# CH340G_adapter.net
KiCad netlist of a schematic drawn in EAGLE
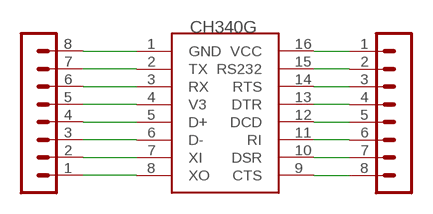
[diagram p0: schematic, sheet 1]

(export (version "E")
  (design (tool "Eeschema 10.0.6"))
  (components
    (comp (ref "SV1")
      (value "MA08-1")
      (footprint "eagle-import:MA08-1")
      (libsource (lib "eagle-import") (part "MA08-1"))
    )
    (comp (ref "SV2")
      (value "MA08-1")
      (footprint "eagle-import:MA08-1")
      (libsource (lib "eagle-import") (part "MA08-1"))
    )
    (comp (ref "U$1")
      (value "CH340G")
      (footprint "eagle-import:SOIC16")
      (libsource (lib "eagle-import") (part "CH340G"))
    )
  )
  (nets
    (net (code "1") (name "Net-(U$1-CTS)") (class "Default")
      (node (ref "SV2") (pin "8") (pinfunction "8_8") (pintype "passive"))
      (node (ref "U$1") (pin "9") (pinfunction "CTS_9") (pintype "bidirectional"))
    )
    (net (code "2") (name "Net-(U$1-D+)") (class "Default")
      (node (ref "SV1") (pin "4") (pinfunction "4_4") (pintype "passive"))
      (node (ref "U$1") (pin "5") (pinfunction "D+_5") (pintype "bidirectional"))
    )
    (net (code "3") (name "Net-(U$1-D-)") (class "Default")
      (node (ref "SV1") (pin "3") (pinfunction "3_3") (pintype "passive"))
      (node (ref "U$1") (pin "6") (pinfunction "D-_6") (pintype "bidirectional"))
    )
    (net (code "4") (name "Net-(U$1-DCD)") (class "Default")
      (node (ref "SV2") (pin "5") (pinfunction "5_5") (pintype "passive"))
      (node (ref "U$1") (pin "12") (pinfunction "DCD_12") (pintype "bidirectional"))
    )
    (net (code "5") (name "Net-(U$1-DSR)") (class "Default")
      (node (ref "SV2") (pin "7") (pinfunction "7_7") (pintype "passive"))
      (node (ref "U$1") (pin "10") (pinfunction "DSR_10") (pintype "bidirectional"))
    )
    (net (code "6") (name "Net-(U$1-DTR)") (class "Default")
      (node (ref "SV2") (pin "4") (pinfunction "4_4") (pintype "passive"))
      (node (ref "U$1") (pin "13") (pinfunction "DTR_13") (pintype "bidirectional"))
    )
    (net (code "7") (name "Net-(U$1-GND)") (class "Default")
      (node (ref "SV1") (pin "8") (pinfunction "8_8") (pintype "passive"))
      (node (ref "U$1") (pin "1") (pinfunction "GND_1") (pintype "bidirectional"))
    )
    (net (code "8") (name "Net-(U$1-RI)") (class "Default")
      (node (ref "SV2") (pin "6") (pinfunction "6_6") (pintype "passive"))
      (node (ref "U$1") (pin "11") (pinfunction "RI_11") (pintype "bidirectional"))
    )
    (net (code "9") (name "Net-(U$1-RS232)") (class "Default")
      (node (ref "SV2") (pin "2") (pinfunction "2_2") (pintype "passive"))
      (node (ref "U$1") (pin "15") (pinfunction "RS232_15") (pintype "bidirectional"))
    )
    (net (code "10") (name "Net-(U$1-RTS)") (class "Default")
      (node (ref "SV2") (pin "3") (pinfunction "3_3") (pintype "passive"))
      (node (ref "U$1") (pin "14") (pinfunction "RTS_14") (pintype "bidirectional"))
    )
    (net (code "11") (name "Net-(U$1-RX)") (class "Default")
      (node (ref "SV1") (pin "6") (pinfunction "6_6") (pintype "passive"))
      (node (ref "U$1") (pin "3") (pinfunction "RX_3") (pintype "bidirectional"))
    )
    (net (code "12") (name "Net-(U$1-TX)") (class "Default")
      (node (ref "SV1") (pin "7") (pinfunction "7_7") (pintype "passive"))
      (node (ref "U$1") (pin "2") (pinfunction "TX_2") (pintype "bidirectional"))
    )
    (net (code "13") (name "Net-(U$1-V3)") (class "Default")
      (node (ref "SV1") (pin "5") (pinfunction "5_5") (pintype "passive"))
      (node (ref "U$1") (pin "4") (pinfunction "V3_4") (pintype "bidirectional"))
    )
    (net (code "14") (name "Net-(U$1-VCC)") (class "Default")
      (node (ref "SV2") (pin "1") (pinfunction "1_1") (pintype "passive"))
      (node (ref "U$1") (pin "16") (pinfunction "VCC_16") (pintype "bidirectional"))
    )
    (net (code "15") (name "Net-(U$1-XI)") (class "Default")
      (node (ref "SV1") (pin "2") (pinfunction "2_2") (pintype "passive"))
      (node (ref "U$1") (pin "7") (pinfunction "XI_7") (pintype "bidirectional"))
    )
    (net (code "16") (name "Net-(U$1-XO)") (class "Default")
      (node (ref "SV1") (pin "1") (pinfunction "1_1") (pintype "passive"))
      (node (ref "U$1") (pin "8") (pinfunction "XO_8") (pintype "bidirectional"))
    )
  )
)
